# imu_b_03_12_2018.net
KiCad netlist of a schematic drawn in EAGLE
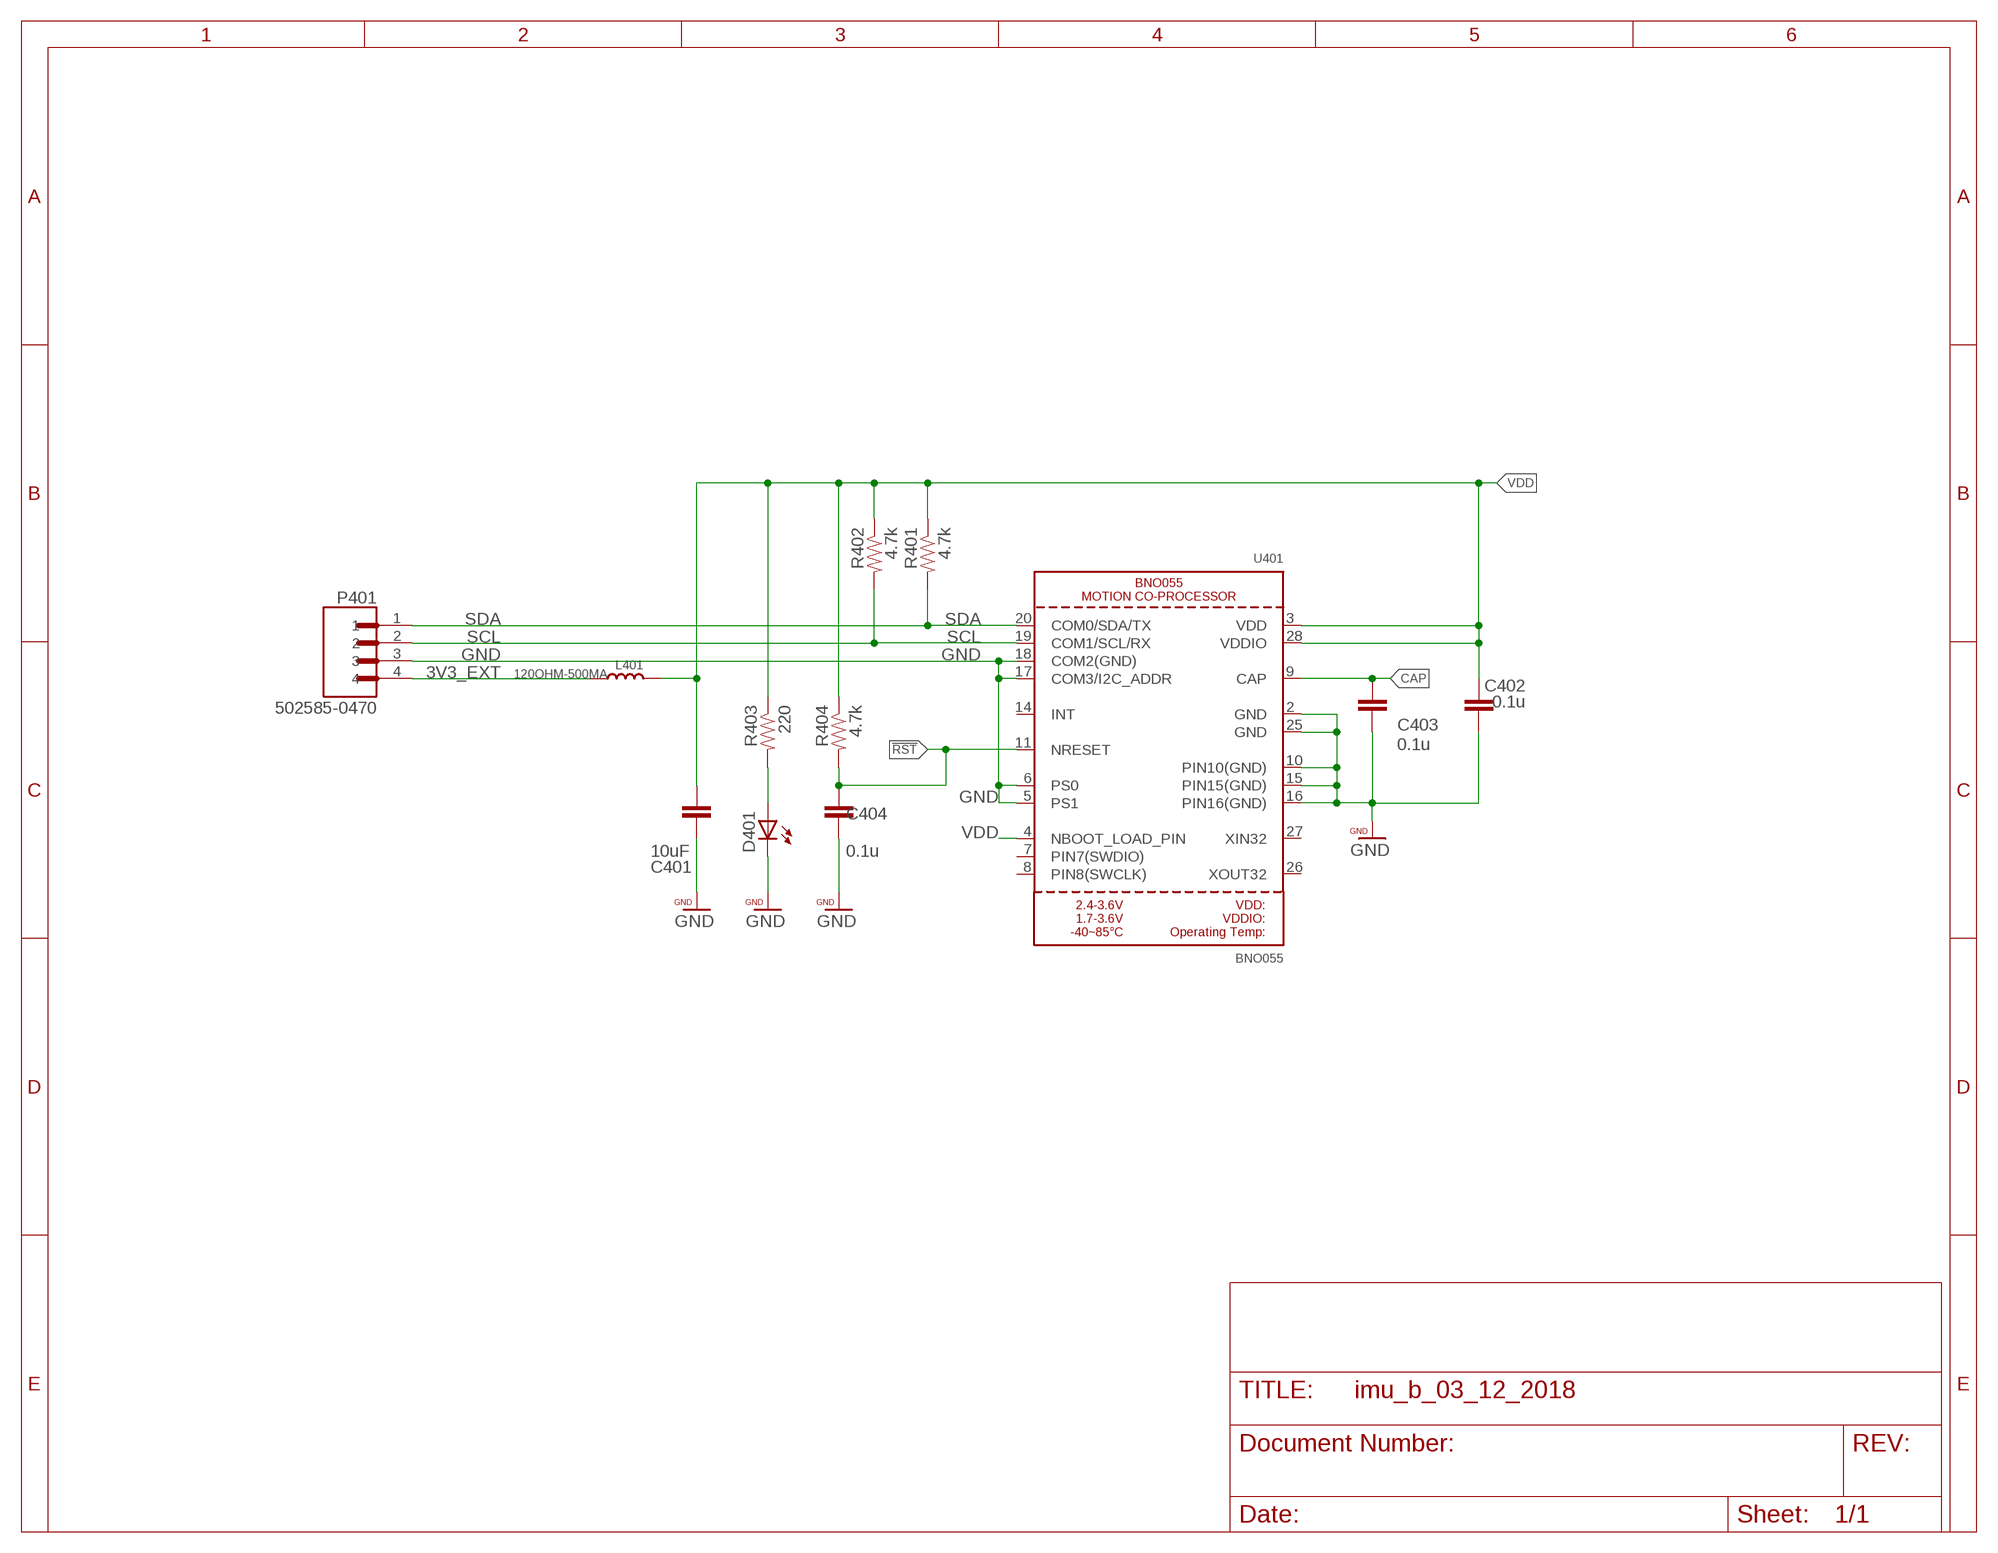
[diagram p0: schematic, sheet 1]

(export (version "E")
  (design (tool "Eeschema 10.0.6"))
  (components
    (comp (ref "C401")
      (value "10uF")
      (footprint "eagle-import:0402-CAP")
      (libsource (lib "eagle-import") (part "CAP0402-CAP"))
    )
    (comp (ref "C402")
      (value "0.1u")
      (footprint "eagle-import:0402-CAP")
      (libsource (lib "eagle-import") (part "CAP0402-CAP"))
    )
    (comp (ref "C403")
      (value "0.1u")
      (footprint "eagle-import:0402-CAP")
      (libsource (lib "eagle-import") (part "CAP0402-CAP"))
    )
    (comp (ref "C404")
      (value "0.1u")
      (footprint "eagle-import:0402-CAP")
      (libsource (lib "eagle-import") (part "CAP0402-CAP"))
    )
    (comp (ref "D401")
      (value "LEDCHIP-LED0603")
      (footprint "eagle-import:CHIP-LED0603")
      (libsource (lib "eagle-import") (part "LEDCHIP-LED0603"))
    )
    (comp (ref "L401")
      (value "120OHM-500MA")
      (footprint "eagle-import:L0603")
      (fields (field (name "MPN") "BLM18AG121SN1D"))
      (libsource (lib "eagle-import") (part "SMD-FERRITE-CHIP-120-OHM-500MA(0603)"))
    )
    (comp (ref "P401")
      (value "502585-0470")
      (footprint "eagle-import:MOLEX_502585-0470")
      (fields (field (name "MF") "Molex"))
      (libsource (lib "eagle-import") (part "502585-0470"))
    )
    (comp (ref "R401")
      (value "4.7k")
      (footprint "eagle-import:EIA-0402")
      (libsource (lib "eagle-import") (part "RESISTOR0402-TYP"))
    )
    (comp (ref "R402")
      (value "4.7k")
      (footprint "eagle-import:EIA-0402")
      (libsource (lib "eagle-import") (part "RESISTOR0402-TYP"))
    )
    (comp (ref "R403")
      (value "220")
      (footprint "eagle-import:EIA-0402")
      (libsource (lib "eagle-import") (part "RESISTOR0402-TYP"))
    )
    (comp (ref "R404")
      (value "4.7k")
      (footprint "eagle-import:EIA-0402")
      (libsource (lib "eagle-import") (part "RESISTOR0402-TYP"))
    )
    (comp (ref "U401")
      (value "BNO055")
      (footprint "eagle-import:BNO055")
      (libsource (lib "eagle-import") (part "BNO055"))
    )
  )
  (nets
    (net (code "1") (name "/3V3_EXT") (class "Default")
      (node (ref "L401") (pin "2") (pinfunction "2_2") (pintype "passive"))
      (node (ref "P401") (pin "4") (pinfunction "4_4") (pintype "passive"))
    )
    (net (code "2") (name "/SCL") (class "Default")
      (node (ref "P401") (pin "2") (pinfunction "2_2") (pintype "passive"))
      (node (ref "R402") (pin "2") (pinfunction "2_2") (pintype "passive"))
      (node (ref "U401") (pin "19") (pinfunction "COM1/SCL/RX_19") (pintype "bidirectional"))
    )
    (net (code "3") (name "/SDA") (class "Default")
      (node (ref "P401") (pin "1") (pinfunction "1_1") (pintype "passive"))
      (node (ref "R401") (pin "2") (pinfunction "2_2") (pintype "passive"))
      (node (ref "U401") (pin "20") (pinfunction "COM0/SDA/TX_20") (pintype "bidirectional"))
    )
    (net (code "4") (name "/~{RST}") (class "Default")
      (node (ref "C404") (pin "1") (pinfunction "1_1") (pintype "passive"))
      (node (ref "R404") (pin "2") (pinfunction "2_2") (pintype "passive"))
      (node (ref "U401") (pin "11") (pinfunction "NRESET_11") (pintype "bidirectional"))
    )
    (net (code "5") (name "CAP") (class "Default")
      (node (ref "C403") (pin "1") (pinfunction "1_1") (pintype "passive"))
      (node (ref "U401") (pin "9") (pinfunction "CAP_9") (pintype "passive"))
    )
    (net (code "6") (name "GND") (class "Default")
      (node (ref "C401") (pin "2") (pinfunction "2_2") (pintype "passive"))
      (node (ref "C402") (pin "2") (pinfunction "2_2") (pintype "passive"))
      (node (ref "C403") (pin "2") (pinfunction "2_2") (pintype "passive"))
      (node (ref "C404") (pin "2") (pinfunction "2_2") (pintype "passive"))
      (node (ref "D401") (pin "C") (pinfunction "C_C") (pintype "passive"))
      (node (ref "P401") (pin "3") (pinfunction "3_3") (pintype "passive"))
      (node (ref "U401") (pin "10") (pinfunction "PIN10(GND)_10") (pintype "bidirectional"))
      (node (ref "U401") (pin "15") (pinfunction "PIN15(GND)_15") (pintype "bidirectional"))
      (node (ref "U401") (pin "16") (pinfunction "PIN16(GND)_16") (pintype "bidirectional"))
      (node (ref "U401") (pin "17") (pinfunction "COM3/I2C_ADDR_17") (pintype "bidirectional"))
      (node (ref "U401") (pin "18") (pinfunction "COM2(GND)_18") (pintype "bidirectional"))
      (node (ref "U401") (pin "2") (pinfunction "GND_2") (pintype "power_in"))
      (node (ref "U401") (pin "25") (pinfunction "GND_25") (pintype "power_in"))
      (node (ref "U401") (pin "5") (pinfunction "PS1_5") (pintype "input"))
      (node (ref "U401") (pin "6") (pinfunction "PS0_6") (pintype "input"))
    )
    (net (code "7") (name "Net-(D401-PadA)") (class "Default")
      (node (ref "D401") (pin "A") (pinfunction "A_A") (pintype "passive"))
      (node (ref "R403") (pin "2") (pinfunction "2_2") (pintype "passive"))
    )
    (net (code "8") (name "VDD") (class "Default")
      (node (ref "C401") (pin "1") (pinfunction "1_1") (pintype "passive"))
      (node (ref "C402") (pin "1") (pinfunction "1_1") (pintype "passive"))
      (node (ref "L401") (pin "1") (pinfunction "1_1") (pintype "passive"))
      (node (ref "R401") (pin "1") (pinfunction "1_1") (pintype "passive"))
      (node (ref "R402") (pin "1") (pinfunction "1_1") (pintype "passive"))
      (node (ref "R403") (pin "1") (pinfunction "1_1") (pintype "passive"))
      (node (ref "R404") (pin "1") (pinfunction "1_1") (pintype "passive"))
      (node (ref "U401") (pin "28") (pinfunction "VDDIO_28") (pintype "power_in"))
      (node (ref "U401") (pin "3") (pinfunction "VDD_3") (pintype "power_in"))
      (node (ref "U401") (pin "4") (pinfunction "NBOOT_LOAD_PIN_4") (pintype "bidirectional"))
    )
    (net (code "9") (name "unconnected-(U401-INT-Pad14)") (class "Default")
      (node (ref "U401") (pin "14") (pinfunction "INT_14") (pintype "output"))
    )
    (net (code "10") (name "unconnected-(U401-PIN7(SWDIO)-Pad7)") (class "Default")
      (node (ref "U401") (pin "7") (pinfunction "PIN7(SWDIO)_7") (pintype "bidirectional"))
    )
    (net (code "11") (name "unconnected-(U401-PIN8(SWCLK)-Pad8)") (class "Default")
      (node (ref "U401") (pin "8") (pinfunction "PIN8(SWCLK)_8") (pintype "bidirectional"))
    )
    (net (code "12") (name "unconnected-(U401-XIN32-Pad27)") (class "Default")
      (node (ref "U401") (pin "27") (pinfunction "XIN32_27") (pintype "input"))
    )
    (net (code "13") (name "unconnected-(U401-XOUT32-Pad26)") (class "Default")
      (node (ref "U401") (pin "26") (pinfunction "XOUT32_26") (pintype "output"))
    )
  )
)
